# 3_v1.net
KiCad netlist of a schematic drawn in Altium Designer
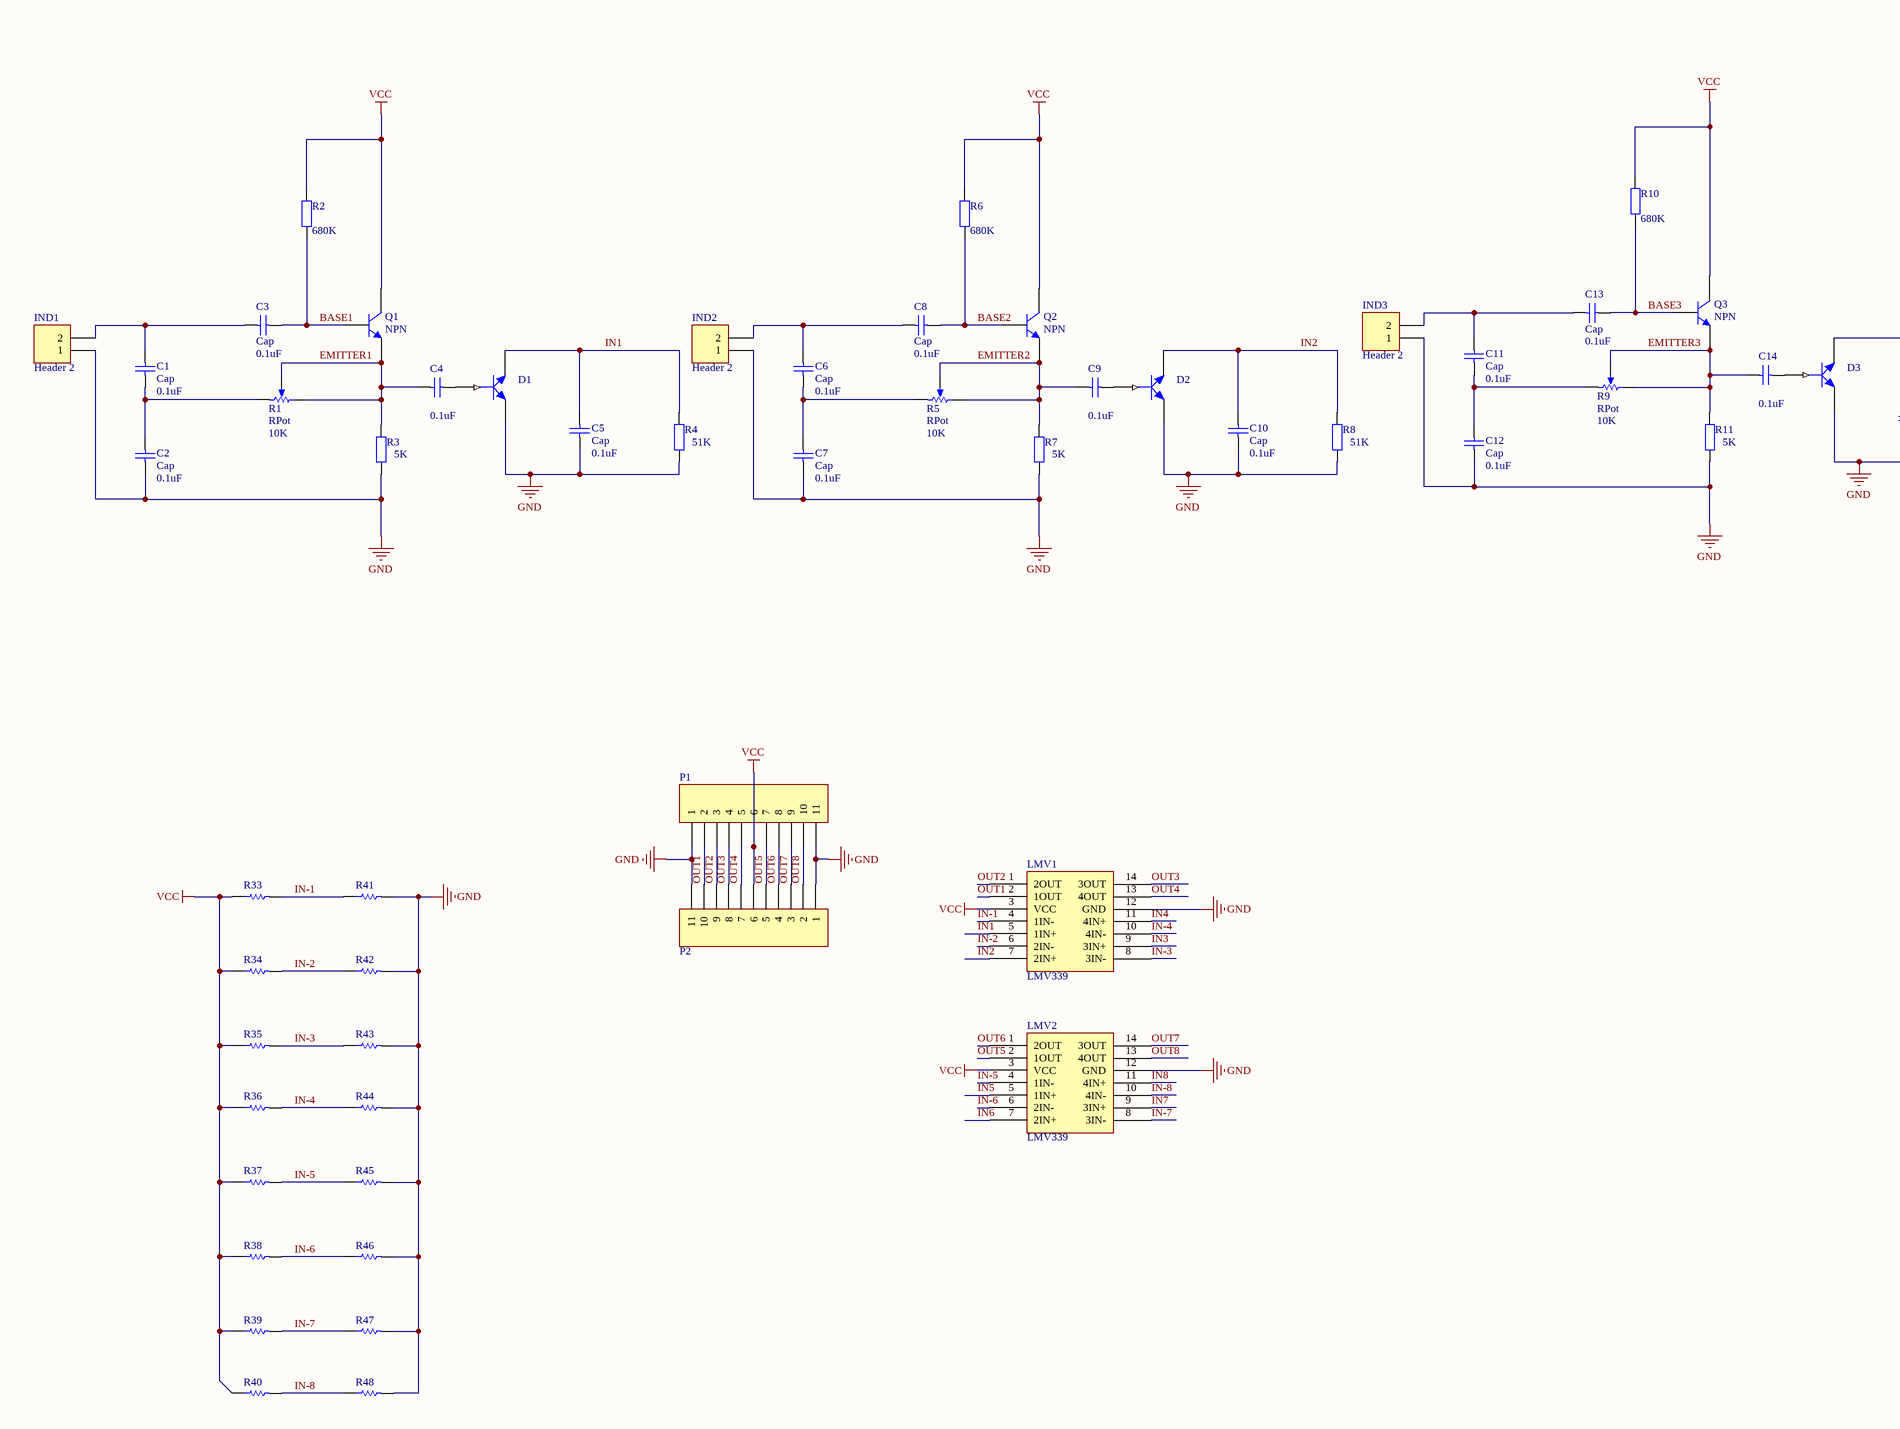
[diagram p0: 3点震荡v1.SchDoc, left]
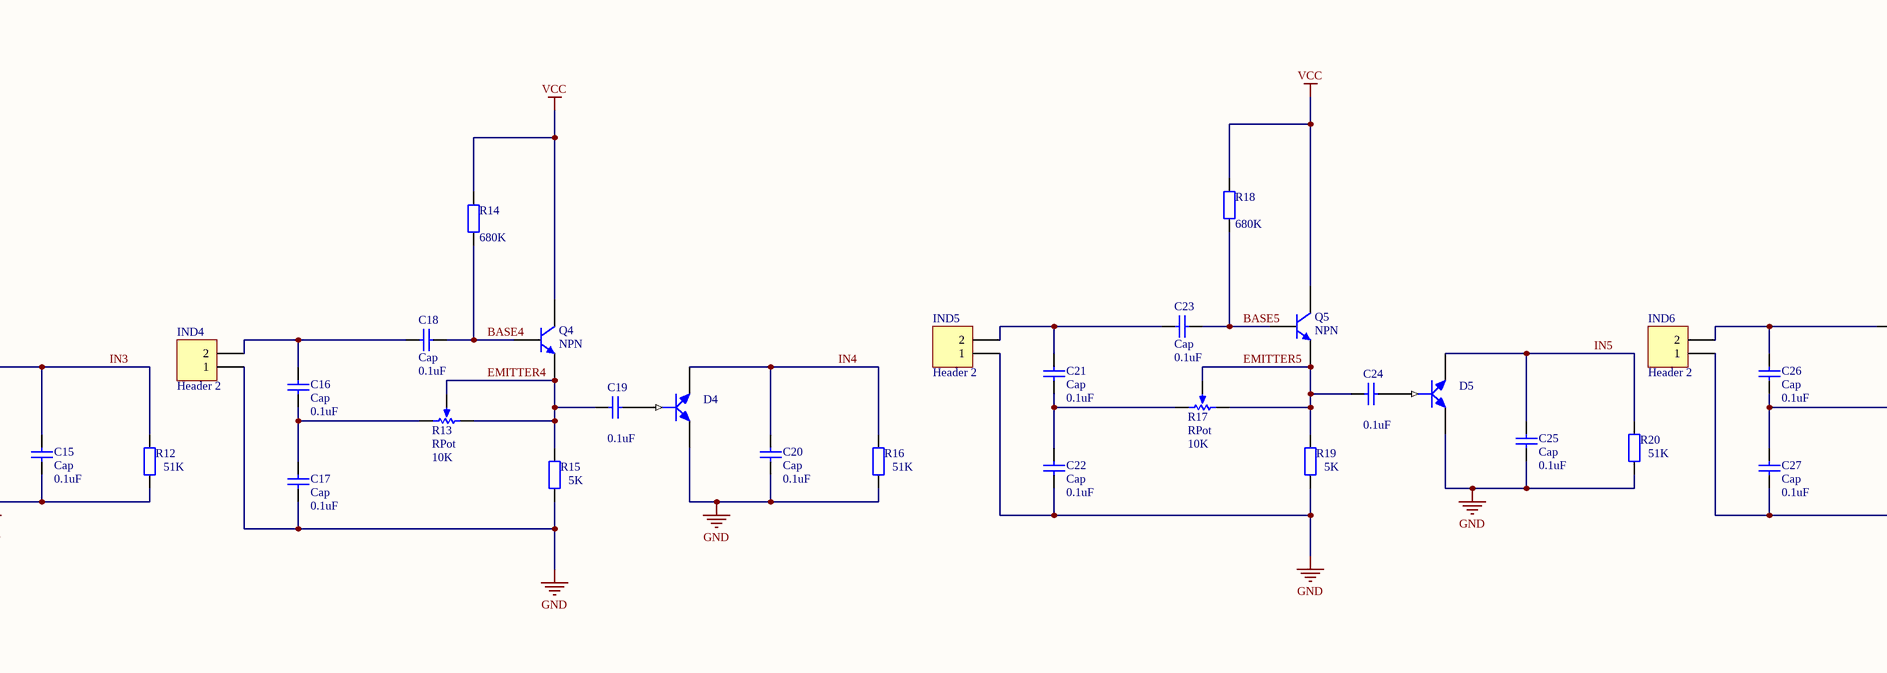
[diagram p1: 3点震荡v1.SchDoc, middle]
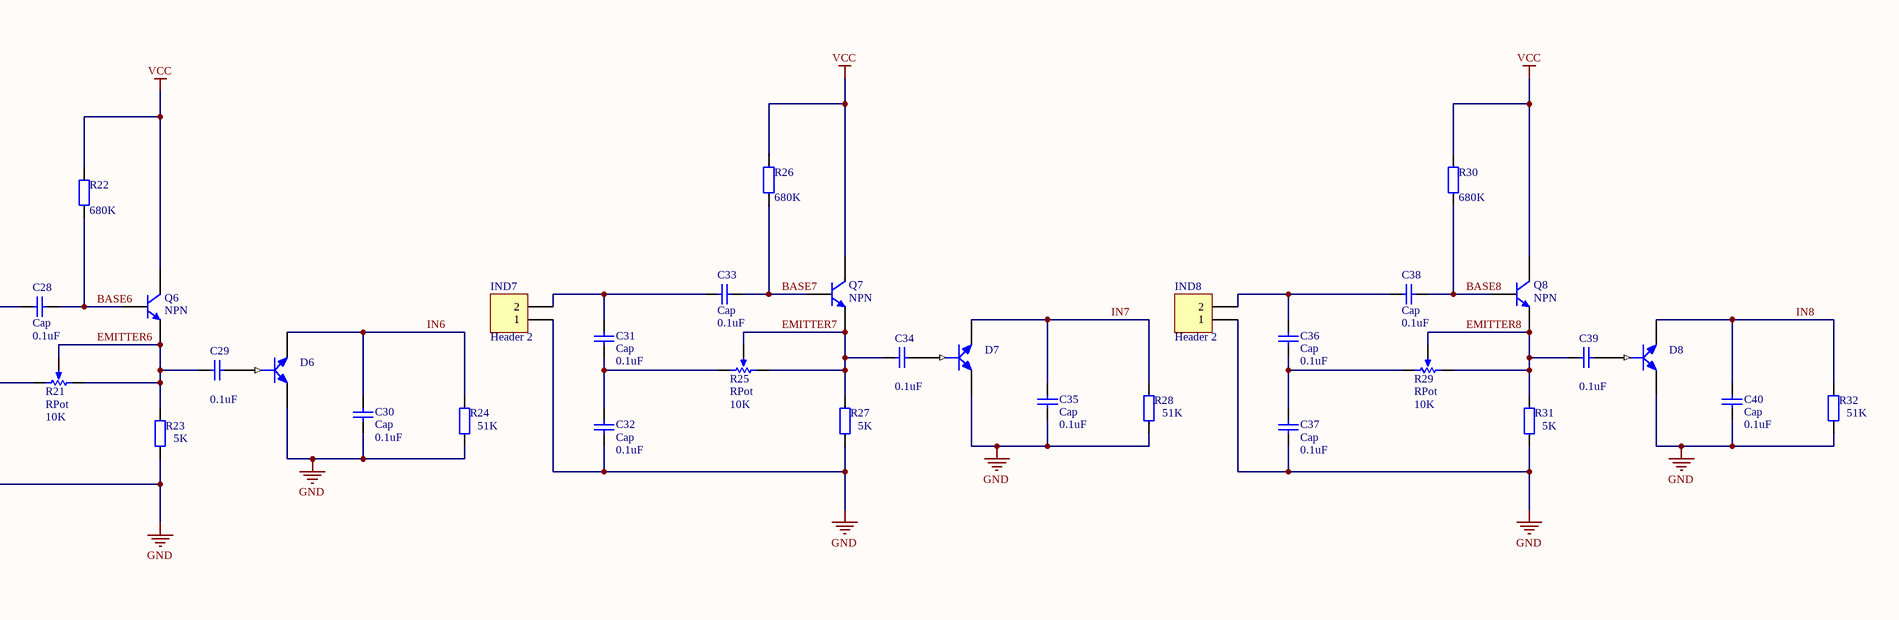
[diagram p2: 3点震荡v1.SchDoc, right]

(export (version "E")
  (design (tool "Eeschema 10.0.6"))
  (components
    (comp (ref "C1")
      (value "Cap")
      (footprint "C2012")
      (description "Capacitor")
      (fields (field (name "ALTIUM_VALUE") "0.1uF"))
      (libsource (lib "Miscellaneous Devices") (part "Cap"))
    )
    (comp (ref "C2")
      (value "Cap")
      (footprint "C2012")
      (description "Capacitor")
      (fields (field (name "ALTIUM_VALUE") "0.1uF"))
      (libsource (lib "Miscellaneous Devices") (part "Cap"))
    )
    (comp (ref "C3")
      (value "Cap")
      (footprint "C2012")
      (description "Capacitor")
      (fields (field (name "ALTIUM_VALUE") "0.1uF"))
      (libsource (lib "Miscellaneous Devices") (part "Cap"))
    )
    (comp (ref "C4")
      (value "0.1uF")
      (footprint "C2012")
      (description "Capacitor")
      (fields (field (name "Comment") "Cap"))
      (libsource (lib "Miscellaneous Devices") (part "Cap"))
    )
    (comp (ref "C5")
      (value "Cap")
      (footprint "c2012")
      (description "Capacitor")
      (fields (field (name "ALTIUM_VALUE") "0.1uF"))
      (libsource (lib "Miscellaneous Devices") (part "Cap"))
    )
    (comp (ref "C6")
      (value "Cap")
      (footprint "C2012")
      (description "Capacitor")
      (fields (field (name "ALTIUM_VALUE") "0.1uF"))
      (libsource (lib "Miscellaneous Devices") (part "Cap"))
    )
    (comp (ref "C7")
      (value "Cap")
      (footprint "C2012")
      (description "Capacitor")
      (fields (field (name "ALTIUM_VALUE") "0.1uF"))
      (libsource (lib "Miscellaneous Devices") (part "Cap"))
    )
    (comp (ref "C8")
      (value "Cap")
      (footprint "C2012")
      (description "Capacitor")
      (fields (field (name "ALTIUM_VALUE") "0.1uF"))
      (libsource (lib "Miscellaneous Devices") (part "Cap"))
    )
    (comp (ref "C9")
      (value "0.1uF")
      (footprint "C2012")
      (description "Capacitor")
      (fields (field (name "Comment") "Cap"))
      (libsource (lib "Miscellaneous Devices") (part "Cap"))
    )
    (comp (ref "C10")
      (value "Cap")
      (footprint "c2012")
      (description "Capacitor")
      (fields (field (name "ALTIUM_VALUE") "0.1uF"))
      (libsource (lib "Miscellaneous Devices") (part "Cap"))
    )
    (comp (ref "C11")
      (value "Cap")
      (footprint "C2012")
      (description "Capacitor")
      (fields (field (name "ALTIUM_VALUE") "0.1uF"))
      (libsource (lib "Miscellaneous Devices") (part "Cap"))
    )
    (comp (ref "C12")
      (value "Cap")
      (footprint "C2012")
      (description "Capacitor")
      (fields (field (name "ALTIUM_VALUE") "0.1uF"))
      (libsource (lib "Miscellaneous Devices") (part "Cap"))
    )
    (comp (ref "C13")
      (value "Cap")
      (footprint "C2012")
      (description "Capacitor")
      (fields (field (name "ALTIUM_VALUE") "0.1uF"))
      (libsource (lib "Miscellaneous Devices") (part "Cap"))
    )
    (comp (ref "C14")
      (value "0.1uF")
      (footprint "C2012")
      (description "Capacitor")
      (fields (field (name "Comment") "Cap"))
      (libsource (lib "Miscellaneous Devices") (part "Cap"))
    )
    (comp (ref "C15")
      (value "Cap")
      (footprint "c2012")
      (description "Capacitor")
      (fields (field (name "ALTIUM_VALUE") "0.1uF"))
      (libsource (lib "Miscellaneous Devices") (part "Cap"))
    )
    (comp (ref "C16")
      (value "Cap")
      (footprint "C2012")
      (description "Capacitor")
      (fields (field (name "ALTIUM_VALUE") "0.1uF"))
      (libsource (lib "Miscellaneous Devices") (part "Cap"))
    )
    (comp (ref "C17")
      (value "Cap")
      (footprint "C2012")
      (description "Capacitor")
      (fields (field (name "ALTIUM_VALUE") "0.1uF"))
      (libsource (lib "Miscellaneous Devices") (part "Cap"))
    )
    (comp (ref "C18")
      (value "Cap")
      (footprint "C2012")
      (description "Capacitor")
      (fields (field (name "ALTIUM_VALUE") "0.1uF"))
      (libsource (lib "Miscellaneous Devices") (part "Cap"))
    )
    (comp (ref "C19")
      (value "0.1uF")
      (footprint "C2012")
      (description "Capacitor")
      (fields (field (name "Comment") "Cap"))
      (libsource (lib "Miscellaneous Devices") (part "Cap"))
    )
    (comp (ref "C20")
      (value "Cap")
      (footprint "c2012")
      (description "Capacitor")
      (fields (field (name "ALTIUM_VALUE") "0.1uF"))
      (libsource (lib "Miscellaneous Devices") (part "Cap"))
    )
    (comp (ref "C21")
      (value "Cap")
      (footprint "C2012")
      (description "Capacitor")
      (fields (field (name "ALTIUM_VALUE") "0.1uF"))
      (libsource (lib "Miscellaneous Devices") (part "Cap"))
    )
    (comp (ref "C22")
      (value "Cap")
      (footprint "C2012")
      (description "Capacitor")
      (fields (field (name "ALTIUM_VALUE") "0.1uF"))
      (libsource (lib "Miscellaneous Devices") (part "Cap"))
    )
    (comp (ref "C23")
      (value "Cap")
      (footprint "C2012")
      (description "Capacitor")
      (fields (field (name "ALTIUM_VALUE") "0.1uF"))
      (libsource (lib "Miscellaneous Devices") (part "Cap"))
    )
    (comp (ref "C24")
      (value "0.1uF")
      (footprint "C2012")
      (description "Capacitor")
      (fields (field (name "Comment") "Cap"))
      (libsource (lib "Miscellaneous Devices") (part "Cap"))
    )
    (comp (ref "C25")
      (value "Cap")
      (footprint "c2012")
      (description "Capacitor")
      (fields (field (name "ALTIUM_VALUE") "0.1uF"))
      (libsource (lib "Miscellaneous Devices") (part "Cap"))
    )
    (comp (ref "C26")
      (value "Cap")
      (footprint "C2012")
      (description "Capacitor")
      (fields (field (name "ALTIUM_VALUE") "0.1uF"))
      (libsource (lib "Miscellaneous Devices") (part "Cap"))
    )
    (comp (ref "C27")
      (value "Cap")
      (footprint "C2012")
      (description "Capacitor")
      (fields (field (name "ALTIUM_VALUE") "0.1uF"))
      (libsource (lib "Miscellaneous Devices") (part "Cap"))
    )
    (comp (ref "C28")
      (value "Cap")
      (footprint "C2012")
      (description "Capacitor")
      (fields (field (name "ALTIUM_VALUE") "0.1uF"))
      (libsource (lib "Miscellaneous Devices") (part "Cap"))
    )
    (comp (ref "C29")
      (value "0.1uF")
      (footprint "C2012")
      (description "Capacitor")
      (fields (field (name "Comment") "Cap"))
      (libsource (lib "Miscellaneous Devices") (part "Cap"))
    )
    (comp (ref "C30")
      (value "Cap")
      (footprint "c2012")
      (description "Capacitor")
      (fields (field (name "ALTIUM_VALUE") "0.1uF"))
      (libsource (lib "Miscellaneous Devices") (part "Cap"))
    )
    (comp (ref "C31")
      (value "Cap")
      (footprint "C2012")
      (description "Capacitor")
      (fields (field (name "ALTIUM_VALUE") "0.1uF"))
      (libsource (lib "Miscellaneous Devices") (part "Cap"))
    )
    (comp (ref "C32")
      (value "Cap")
      (footprint "C2012")
      (description "Capacitor")
      (fields (field (name "ALTIUM_VALUE") "0.1uF"))
      (libsource (lib "Miscellaneous Devices") (part "Cap"))
    )
    (comp (ref "C33")
      (value "Cap")
      (footprint "C2012")
      (description "Capacitor")
      (fields (field (name "ALTIUM_VALUE") "0.1uF"))
      (libsource (lib "Miscellaneous Devices") (part "Cap"))
    )
    (comp (ref "C34")
      (value "0.1uF")
      (footprint "C2012")
      (description "Capacitor")
      (fields (field (name "Comment") "Cap"))
      (libsource (lib "Miscellaneous Devices") (part "Cap"))
    )
    (comp (ref "C35")
      (value "Cap")
      (footprint "c2012")
      (description "Capacitor")
      (fields (field (name "ALTIUM_VALUE") "0.1uF"))
      (libsource (lib "Miscellaneous Devices") (part "Cap"))
    )
    (comp (ref "C36")
      (value "Cap")
      (footprint "C2012")
      (description "Capacitor")
      (fields (field (name "ALTIUM_VALUE") "0.1uF"))
      (libsource (lib "Miscellaneous Devices") (part "Cap"))
    )
    (comp (ref "C37")
      (value "Cap")
      (footprint "C2012")
      (description "Capacitor")
      (fields (field (name "ALTIUM_VALUE") "0.1uF"))
      (libsource (lib "Miscellaneous Devices") (part "Cap"))
    )
    (comp (ref "C38")
      (value "Cap")
      (footprint "C2012")
      (description "Capacitor")
      (fields (field (name "ALTIUM_VALUE") "0.1uF"))
      (libsource (lib "Miscellaneous Devices") (part "Cap"))
    )
    (comp (ref "C39")
      (value "0.1uF")
      (footprint "C2012")
      (description "Capacitor")
      (fields (field (name "Comment") "Cap"))
      (libsource (lib "Miscellaneous Devices") (part "Cap"))
    )
    (comp (ref "C40")
      (value "Cap")
      (footprint "c2012")
      (description "Capacitor")
      (fields (field (name "ALTIUM_VALUE") "0.1uF"))
      (libsource (lib "Miscellaneous Devices") (part "Cap"))
    )
    (comp (ref "D1")
      (value "Diac-NPN")
      (footprint "SOT23_N")
      (description "DIAC")
      (libsource (lib "Miscellaneous Devices") (part "Diac-NPN"))
    )
    (comp (ref "D2")
      (value "Diac-NPN")
      (footprint "SOT23_N")
      (description "DIAC")
      (libsource (lib "Miscellaneous Devices") (part "Diac-NPN"))
    )
    (comp (ref "D3")
      (value "Diac-NPN")
      (footprint "SOT23_N")
      (description "DIAC")
      (libsource (lib "Miscellaneous Devices") (part "Diac-NPN"))
    )
    (comp (ref "D4")
      (value "Diac-NPN")
      (footprint "SOT23_N")
      (description "DIAC")
      (libsource (lib "Miscellaneous Devices") (part "Diac-NPN"))
    )
    (comp (ref "D5")
      (value "Diac-NPN")
      (footprint "SOT23_N")
      (description "DIAC")
      (libsource (lib "Miscellaneous Devices") (part "Diac-NPN"))
    )
    (comp (ref "D6")
      (value "Diac-NPN")
      (footprint "SOT23_N")
      (description "DIAC")
      (libsource (lib "Miscellaneous Devices") (part "Diac-NPN"))
    )
    (comp (ref "D7")
      (value "Diac-NPN")
      (footprint "SOT23_N")
      (description "DIAC")
      (libsource (lib "Miscellaneous Devices") (part "Diac-NPN"))
    )
    (comp (ref "D8")
      (value "Diac-NPN")
      (footprint "SOT23_N")
      (description "DIAC")
      (libsource (lib "Miscellaneous Devices") (part "Diac-NPN"))
    )
    (comp (ref "IND1")
      (value "Header 2")
      (footprint "HDR1X2")
      (description "Header, 2-Pin")
      (libsource (lib "Sparks") (part "Header 2"))
    )
    (comp (ref "IND2")
      (value "Header 2")
      (footprint "HDR1X2")
      (description "Header, 2-Pin")
      (libsource (lib "Sparks") (part "Header 2"))
    )
    (comp (ref "IND3")
      (value "Header 2")
      (footprint "HDR1X2")
      (description "Header, 2-Pin")
      (libsource (lib "Sparks") (part "Header 2"))
    )
    (comp (ref "IND4")
      (value "Header 2")
      (footprint "HDR1X2")
      (description "Header, 2-Pin")
      (libsource (lib "Sparks") (part "Header 2"))
    )
    (comp (ref "IND5")
      (value "Header 2")
      (footprint "HDR1X2")
      (description "Header, 2-Pin")
      (libsource (lib "Sparks") (part "Header 2"))
    )
    (comp (ref "IND6")
      (value "Header 2")
      (footprint "HDR1X2")
      (description "Header, 2-Pin")
      (libsource (lib "Sparks") (part "Header 2"))
    )
    (comp (ref "IND7")
      (value "Header 2")
      (footprint "HDR1X2")
      (description "Header, 2-Pin")
      (libsource (lib "Sparks") (part "Header 2"))
    )
    (comp (ref "IND8")
      (value "Header 2")
      (footprint "HDR1X2")
      (description "Header, 2-Pin")
      (libsource (lib "Sparks") (part "Header 2"))
    )
    (comp (ref "LMV1") (value "LMV339") (footprint "LMV339 TSSOP14") (libsource (lib "2号库") (part "LMV339")))
    (comp (ref "LMV2") (value "LMV339") (footprint "LMV339 TSSOP14") (libsource (lib "2号库") (part "LMV339")))
    (comp (ref "P1")
      (value "Header 11")
      (footprint "HDR1X11")
      (description "Header, 11-Pin")
      (libsource (lib "Sparks") (part "Header 11"))
    )
    (comp (ref "P2")
      (value "Header 11")
      (footprint "FFC/SM1.0-2H11")
      (description "Header, 11-Pin")
      (libsource (lib "") (part "Header 11_1"))
    )
    (comp (ref "Q1")
      (value "NPN")
      (footprint "SOT23_N")
      (description "NPN Bipolar Transistor")
      (libsource (lib "Miscellaneous Devices") (part "NPN"))
    )
    (comp (ref "Q2")
      (value "NPN")
      (footprint "SOT23_N")
      (description "NPN Bipolar Transistor")
      (libsource (lib "Miscellaneous Devices") (part "NPN"))
    )
    (comp (ref "Q3")
      (value "NPN")
      (footprint "SOT23_N")
      (description "NPN Bipolar Transistor")
      (libsource (lib "Miscellaneous Devices") (part "NPN"))
    )
    (comp (ref "Q4")
      (value "NPN")
      (footprint "SOT23_N")
      (description "NPN Bipolar Transistor")
      (libsource (lib "Miscellaneous Devices") (part "NPN"))
    )
    (comp (ref "Q5")
      (value "NPN")
      (footprint "SOT23_N")
      (description "NPN Bipolar Transistor")
      (libsource (lib "Miscellaneous Devices") (part "NPN"))
    )
    (comp (ref "Q6")
      (value "NPN")
      (footprint "SOT23_N")
      (description "NPN Bipolar Transistor")
      (libsource (lib "Miscellaneous Devices") (part "NPN"))
    )
    (comp (ref "Q7")
      (value "NPN")
      (footprint "SOT23_N")
      (description "NPN Bipolar Transistor")
      (libsource (lib "Miscellaneous Devices") (part "NPN"))
    )
    (comp (ref "Q8")
      (value "NPN")
      (footprint "SOT23_N")
      (description "NPN Bipolar Transistor")
      (libsource (lib "Miscellaneous Devices") (part "NPN"))
    )
    (comp (ref "R1")
      (value "RPot")
      (footprint "pot（长方形）")
      (description "Potentiometer")
      (fields (field (name "ALTIUM_VALUE") "10K"))
      (libsource (lib "Miscellaneous Devices") (part "RPot"))
    )
    (comp (ref "R2")
      (value "680K")
      (footprint "r2012")
      (description "Resistor")
      (fields (field (name "Comment") "Res2"))
      (libsource (lib "Miscellaneous Devices") (part "Res2"))
    )
    (comp (ref "R3")
      (value "5K")
      (footprint "R2012")
      (description "Resistor")
      (fields (field (name "Comment") "Res2"))
      (libsource (lib "Miscellaneous Devices") (part "Res2"))
    )
    (comp (ref "R4")
      (value "51K")
      (footprint "R2012")
      (description "Resistor")
      (fields (field (name "Comment") "Res2"))
      (libsource (lib "Miscellaneous Devices") (part "Res2"))
    )
    (comp (ref "R5")
      (value "RPot")
      (footprint "pot（长方形）")
      (description "Potentiometer")
      (fields (field (name "ALTIUM_VALUE") "10K"))
      (libsource (lib "Miscellaneous Devices") (part "RPot"))
    )
    (comp (ref "R6")
      (value "680K")
      (footprint "r2012")
      (description "Resistor")
      (fields (field (name "Comment") "Res2"))
      (libsource (lib "Miscellaneous Devices") (part "Res2"))
    )
    (comp (ref "R7")
      (value "5K")
      (footprint "R2012")
      (description "Resistor")
      (fields (field (name "Comment") "Res2"))
      (libsource (lib "Miscellaneous Devices") (part "Res2"))
    )
    (comp (ref "R8")
      (value "51K")
      (footprint "R2012")
      (description "Resistor")
      (fields (field (name "Comment") "Res2"))
      (libsource (lib "Miscellaneous Devices") (part "Res2"))
    )
    (comp (ref "R9")
      (value "RPot")
      (footprint "pot（长方形）")
      (description "Potentiometer")
      (fields (field (name "ALTIUM_VALUE") "10K"))
      (libsource (lib "Miscellaneous Devices") (part "RPot"))
    )
    (comp (ref "R10")
      (value "680K")
      (footprint "r2012")
      (description "Resistor")
      (fields (field (name "Comment") "Res2"))
      (libsource (lib "Miscellaneous Devices") (part "Res2"))
    )
    (comp (ref "R11")
      (value "5K")
      (footprint "R2012")
      (description "Resistor")
      (fields (field (name "Comment") "Res2"))
      (libsource (lib "Miscellaneous Devices") (part "Res2"))
    )
    (comp (ref "R12")
      (value "51K")
      (footprint "R2012")
      (description "Resistor")
      (fields (field (name "Comment") "Res2"))
      (libsource (lib "Miscellaneous Devices") (part "Res2"))
    )
    (comp (ref "R13")
      (value "RPot")
      (footprint "pot（长方形）")
      (description "Potentiometer")
      (fields (field (name "ALTIUM_VALUE") "10K"))
      (libsource (lib "Miscellaneous Devices") (part "RPot"))
    )
    (comp (ref "R14")
      (value "680K")
      (footprint "r2012")
      (description "Resistor")
      (fields (field (name "Comment") "Res2"))
      (libsource (lib "Miscellaneous Devices") (part "Res2"))
    )
    (comp (ref "R15")
      (value "5K")
      (footprint "R2012")
      (description "Resistor")
      (fields (field (name "Comment") "Res2"))
      (libsource (lib "Miscellaneous Devices") (part "Res2"))
    )
    (comp (ref "R16")
      (value "51K")
      (footprint "R2012")
      (description "Resistor")
      (fields (field (name "Comment") "Res2"))
      (libsource (lib "Miscellaneous Devices") (part "Res2"))
    )
    (comp (ref "R17")
      (value "RPot")
      (footprint "pot（长方形）")
      (description "Potentiometer")
      (fields (field (name "ALTIUM_VALUE") "10K"))
      (libsource (lib "Miscellaneous Devices") (part "RPot"))
    )
    (comp (ref "R18")
      (value "680K")
      (footprint "r2012")
      (description "Resistor")
      (fields (field (name "Comment") "Res2"))
      (libsource (lib "Miscellaneous Devices") (part "Res2"))
    )
    (comp (ref "R19")
      (value "5K")
      (footprint "R2012")
      (description "Resistor")
      (fields (field (name "Comment") "Res2"))
      (libsource (lib "Miscellaneous Devices") (part "Res2"))
    )
    (comp (ref "R20")
      (value "51K")
      (footprint "R2012")
      (description "Resistor")
      (fields (field (name "Comment") "Res2"))
      (libsource (lib "Miscellaneous Devices") (part "Res2"))
    )
    (comp (ref "R21")
      (value "RPot")
      (footprint "pot（长方形）")
      (description "Potentiometer")
      (fields (field (name "ALTIUM_VALUE") "10K"))
      (libsource (lib "Miscellaneous Devices") (part "RPot"))
    )
    (comp (ref "R22")
      (value "680K")
      (footprint "r2012")
      (description "Resistor")
      (fields (field (name "Comment") "Res2"))
      (libsource (lib "Miscellaneous Devices") (part "Res2"))
    )
    (comp (ref "R23")
      (value "5K")
      (footprint "R2012")
      (description "Resistor")
      (fields (field (name "Comment") "Res2"))
      (libsource (lib "Miscellaneous Devices") (part "Res2"))
    )
    (comp (ref "R24")
      (value "51K")
      (footprint "R2012")
      (description "Resistor")
      (fields (field (name "Comment") "Res2"))
      (libsource (lib "Miscellaneous Devices") (part "Res2"))
    )
    (comp (ref "R25")
      (value "RPot")
      (footprint "pot（长方形）")
      (description "Potentiometer")
      (fields (field (name "ALTIUM_VALUE") "10K"))
      (libsource (lib "Miscellaneous Devices") (part "RPot"))
    )
    (comp (ref "R26")
      (value "680K")
      (footprint "r2012")
      (description "Resistor")
      (fields (field (name "Comment") "Res2"))
      (libsource (lib "Miscellaneous Devices") (part "Res2"))
    )
    (comp (ref "R27")
      (value "5K")
      (footprint "R2012")
      (description "Resistor")
      (fields (field (name "Comment") "Res2"))
      (libsource (lib "Miscellaneous Devices") (part "Res2"))
    )
    (comp (ref "R28")
      (value "51K")
      (footprint "R2012")
      (description "Resistor")
      (fields (field (name "Comment") "Res2"))
      (libsource (lib "Miscellaneous Devices") (part "Res2"))
    )
    (comp (ref "R29")
      (value "RPot")
      (footprint "pot（长方形）")
      (description "Potentiometer")
      (fields (field (name "ALTIUM_VALUE") "10K"))
      (libsource (lib "Miscellaneous Devices") (part "RPot"))
    )
    (comp (ref "R30")
      (value "680K")
      (footprint "r2012")
      (description "Resistor")
      (fields (field (name "Comment") "Res2"))
      (libsource (lib "Miscellaneous Devices") (part "Res2"))
    )
    (comp (ref "R31")
      (value "5K")
      (footprint "R2012")
      (description "Resistor")
      (fields (field (name "Comment") "Res2"))
      (libsource (lib "Miscellaneous Devices") (part "Res2"))
    )
    (comp (ref "R32")
      (value "51K")
      (footprint "R2012")
      (description "Resistor")
      (fields (field (name "Comment") "Res2"))
      (libsource (lib "Miscellaneous Devices") (part "Res2"))
    )
    (comp (ref "R33")
      (value "Res")
      (footprint "R2012")
      (description "贴片电阻")
      (libsource (lib "Sparks") (part "Res"))
    )
    (comp (ref "R34")
      (value "Res")
      (footprint "R2012")
      (description "贴片电阻")
      (libsource (lib "Sparks") (part "Res"))
    )
    (comp (ref "R35")
      (value "Res")
      (footprint "R2012")
      (description "贴片电阻")
      (libsource (lib "Sparks") (part "Res"))
    )
    (comp (ref "R36")
      (value "Res")
      (footprint "R2012")
      (description "贴片电阻")
      (libsource (lib "Sparks") (part "Res"))
    )
    (comp (ref "R37")
      (value "Res")
      (footprint "R2012")
      (description "贴片电阻")
      (libsource (lib "Sparks") (part "Res"))
    )
    (comp (ref "R38")
      (value "Res")
      (footprint "R2012")
      (description "贴片电阻")
      (libsource (lib "Sparks") (part "Res"))
    )
    (comp (ref "R39")
      (value "Res")
      (footprint "R2012")
      (description "贴片电阻")
      (libsource (lib "Sparks") (part "Res"))
    )
    (comp (ref "R40")
      (value "Res")
      (footprint "R2012")
      (description "贴片电阻")
      (libsource (lib "Sparks") (part "Res"))
    )
    (comp (ref "R41")
      (value "Res")
      (footprint "R2012")
      (description "贴片电阻")
      (libsource (lib "Sparks") (part "Res"))
    )
    (comp (ref "R42")
      (value "Res")
      (footprint "R2012")
      (description "贴片电阻")
      (libsource (lib "Sparks") (part "Res"))
    )
    (comp (ref "R43")
      (value "Res")
      (footprint "R2012")
      (description "贴片电阻")
      (libsource (lib "Sparks") (part "Res"))
    )
    (comp (ref "R44")
      (value "Res")
      (footprint "R2012")
      (description "贴片电阻")
      (libsource (lib "Sparks") (part "Res"))
    )
    (comp (ref "R45")
      (value "Res")
      (footprint "R2012")
      (description "贴片电阻")
      (libsource (lib "Sparks") (part "Res"))
    )
    (comp (ref "R46")
      (value "Res")
      (footprint "R2012")
      (description "贴片电阻")
      (libsource (lib "Sparks") (part "Res"))
    )
    (comp (ref "R47")
      (value "Res")
      (footprint "R2012")
      (description "贴片电阻")
      (libsource (lib "Sparks") (part "Res"))
    )
    (comp (ref "R48")
      (value "Res")
      (footprint "R2012")
      (description "贴片电阻")
      (libsource (lib "Sparks") (part "Res"))
    )
  )
  (nets
    (net (code "1") (name "/BASE1") (class "Default")
      (node (ref "C3") (pin "1") (pinfunction "1_1") (pintype "passive"))
      (node (ref "Q1") (pin "2") (pinfunction "B_2") (pintype "passive"))
      (node (ref "R2") (pin "1") (pinfunction "1_1") (pintype "passive"))
    )
    (net (code "2") (name "/BASE2") (class "Default")
      (node (ref "C8") (pin "1") (pinfunction "1_1") (pintype "passive"))
      (node (ref "Q2") (pin "2") (pinfunction "B_2") (pintype "passive"))
      (node (ref "R6") (pin "1") (pinfunction "1_1") (pintype "passive"))
    )
    (net (code "3") (name "/BASE3") (class "Default")
      (node (ref "C13") (pin "1") (pinfunction "1_1") (pintype "passive"))
      (node (ref "Q3") (pin "2") (pinfunction "B_2") (pintype "passive"))
      (node (ref "R10") (pin "1") (pinfunction "1_1") (pintype "passive"))
    )
    (net (code "4") (name "/BASE4") (class "Default")
      (node (ref "C18") (pin "1") (pinfunction "1_1") (pintype "passive"))
      (node (ref "Q4") (pin "2") (pinfunction "B_2") (pintype "passive"))
      (node (ref "R14") (pin "1") (pinfunction "1_1") (pintype "passive"))
    )
    (net (code "5") (name "/BASE5") (class "Default")
      (node (ref "C23") (pin "1") (pinfunction "1_1") (pintype "passive"))
      (node (ref "Q5") (pin "2") (pinfunction "B_2") (pintype "passive"))
      (node (ref "R18") (pin "1") (pinfunction "1_1") (pintype "passive"))
    )
    (net (code "6") (name "/BASE6") (class "Default")
      (node (ref "C28") (pin "1") (pinfunction "1_1") (pintype "passive"))
      (node (ref "Q6") (pin "2") (pinfunction "B_2") (pintype "passive"))
      (node (ref "R22") (pin "1") (pinfunction "1_1") (pintype "passive"))
    )
    (net (code "7") (name "/BASE7") (class "Default")
      (node (ref "C33") (pin "1") (pinfunction "1_1") (pintype "passive"))
      (node (ref "Q7") (pin "2") (pinfunction "B_2") (pintype "passive"))
      (node (ref "R26") (pin "1") (pinfunction "1_1") (pintype "passive"))
    )
    (net (code "8") (name "/BASE8") (class "Default")
      (node (ref "C38") (pin "1") (pinfunction "1_1") (pintype "passive"))
      (node (ref "Q8") (pin "2") (pinfunction "B_2") (pintype "passive"))
      (node (ref "R30") (pin "1") (pinfunction "1_1") (pintype "passive"))
    )
    (net (code "9") (name "/EMITTER1") (class "Default")
      (node (ref "C4") (pin "1") (pinfunction "1_1") (pintype "passive"))
      (node (ref "Q1") (pin "3") (pinfunction "E_3") (pintype "passive"))
      (node (ref "R1") (pin "1") (pinfunction "TOP_1") (pintype "passive"))
      (node (ref "R1") (pin "3") (pinfunction "TAP_3") (pintype "passive"))
      (node (ref "R3") (pin "2") (pinfunction "2_2") (pintype "passive"))
    )
    (net (code "10") (name "/EMITTER2") (class "Default")
      (node (ref "C9") (pin "1") (pinfunction "1_1") (pintype "passive"))
      (node (ref "Q2") (pin "3") (pinfunction "E_3") (pintype "passive"))
      (node (ref "R5") (pin "1") (pinfunction "TOP_1") (pintype "passive"))
      (node (ref "R5") (pin "3") (pinfunction "TAP_3") (pintype "passive"))
      (node (ref "R7") (pin "2") (pinfunction "2_2") (pintype "passive"))
    )
    (net (code "11") (name "/EMITTER3") (class "Default")
      (node (ref "C14") (pin "1") (pinfunction "1_1") (pintype "passive"))
      (node (ref "Q3") (pin "3") (pinfunction "E_3") (pintype "passive"))
      (node (ref "R11") (pin "2") (pinfunction "2_2") (pintype "passive"))
      (node (ref "R9") (pin "1") (pinfunction "TOP_1") (pintype "passive"))
      (node (ref "R9") (pin "3") (pinfunction "TAP_3") (pintype "passive"))
    )
    (net (code "12") (name "/EMITTER4") (class "Default")
      (node (ref "C19") (pin "1") (pinfunction "1_1") (pintype "passive"))
      (node (ref "Q4") (pin "3") (pinfunction "E_3") (pintype "passive"))
      (node (ref "R13") (pin "1") (pinfunction "TOP_1") (pintype "passive"))
      (node (ref "R13") (pin "3") (pinfunction "TAP_3") (pintype "passive"))
      (node (ref "R15") (pin "2") (pinfunction "2_2") (pintype "passive"))
    )
    (net (code "13") (name "/EMITTER5") (class "Default")
      (node (ref "C24") (pin "1") (pinfunction "1_1") (pintype "passive"))
      (node (ref "Q5") (pin "3") (pinfunction "E_3") (pintype "passive"))
      (node (ref "R17") (pin "1") (pinfunction "TOP_1") (pintype "passive"))
      (node (ref "R17") (pin "3") (pinfunction "TAP_3") (pintype "passive"))
      (node (ref "R19") (pin "2") (pinfunction "2_2") (pintype "passive"))
    )
    (net (code "14") (name "/EMITTER6") (class "Default")
      (node (ref "C29") (pin "1") (pinfunction "1_1") (pintype "passive"))
      (node (ref "Q6") (pin "3") (pinfunction "E_3") (pintype "passive"))
      (node (ref "R21") (pin "1") (pinfunction "TOP_1") (pintype "passive"))
      (node (ref "R21") (pin "3") (pinfunction "TAP_3") (pintype "passive"))
      (node (ref "R23") (pin "2") (pinfunction "2_2") (pintype "passive"))
    )
    (net (code "15") (name "/EMITTER7") (class "Default")
      (node (ref "C34") (pin "1") (pinfunction "1_1") (pintype "passive"))
      (node (ref "Q7") (pin "3") (pinfunction "E_3") (pintype "passive"))
      (node (ref "R25") (pin "1") (pinfunction "TOP_1") (pintype "passive"))
      (node (ref "R25") (pin "3") (pinfunction "TAP_3") (pintype "passive"))
      (node (ref "R27") (pin "2") (pinfunction "2_2") (pintype "passive"))
    )
    (net (code "16") (name "/EMITTER8") (class "Default")
      (node (ref "C39") (pin "1") (pinfunction "1_1") (pintype "passive"))
      (node (ref "Q8") (pin "3") (pinfunction "E_3") (pintype "passive"))
      (node (ref "R29") (pin "1") (pinfunction "TOP_1") (pintype "passive"))
      (node (ref "R29") (pin "3") (pinfunction "TAP_3") (pintype "passive"))
      (node (ref "R31") (pin "2") (pinfunction "2_2") (pintype "passive"))
    )
    (net (code "17") (name "/IN-1") (class "Default")
      (node (ref "LMV1") (pin "4") (pinfunction "1IN-_4") (pintype "passive"))
      (node (ref "R33") (pin "2") (pinfunction "2_2") (pintype "passive"))
      (node (ref "R41") (pin "1") (pinfunction "1_1") (pintype "passive"))
    )
    (net (code "18") (name "/IN-2") (class "Default")
      (node (ref "LMV1") (pin "6") (pinfunction "2IN-_6") (pintype "passive"))
      (node (ref "R34") (pin "2") (pinfunction "2_2") (pintype "passive"))
      (node (ref "R42") (pin "1") (pinfunction "1_1") (pintype "passive"))
    )
    (net (code "19") (name "/IN-3") (class "Default")
      (node (ref "LMV1") (pin "8") (pinfunction "3IN-_8") (pintype "passive"))
      (node (ref "R35") (pin "2") (pinfunction "2_2") (pintype "passive"))
      (node (ref "R43") (pin "1") (pinfunction "1_1") (pintype "passive"))
    )
    (net (code "20") (name "/IN-4") (class "Default")
      (node (ref "LMV1") (pin "10") (pinfunction "4IN-_10") (pintype "passive"))
      (node (ref "R36") (pin "2") (pinfunction "2_2") (pintype "passive"))
      (node (ref "R44") (pin "1") (pinfunction "1_1") (pintype "passive"))
    )
    (net (code "21") (name "/IN-5") (class "Default")
      (node (ref "LMV2") (pin "4") (pinfunction "1IN-_4") (pintype "passive"))
      (node (ref "R37") (pin "2") (pinfunction "2_2") (pintype "passive"))
      (node (ref "R45") (pin "1") (pinfunction "1_1") (pintype "passive"))
    )
    (net (code "22") (name "/IN-6") (class "Default")
      (node (ref "LMV2") (pin "6") (pinfunction "2IN-_6") (pintype "passive"))
      (node (ref "R38") (pin "2") (pinfunction "2_2") (pintype "passive"))
      (node (ref "R46") (pin "1") (pinfunction "1_1") (pintype "passive"))
    )
    (net (code "23") (name "/IN-7") (class "Default")
      (node (ref "LMV2") (pin "8") (pinfunction "3IN-_8") (pintype "passive"))
      (node (ref "R39") (pin "2") (pinfunction "2_2") (pintype "passive"))
      (node (ref "R47") (pin "1") (pinfunction "1_1") (pintype "passive"))
    )
    (net (code "24") (name "/IN-8") (class "Default")
      (node (ref "LMV2") (pin "10") (pinfunction "4IN-_10") (pintype "passive"))
      (node (ref "R40") (pin "2") (pinfunction "2_2") (pintype "passive"))
      (node (ref "R48") (pin "1") (pinfunction "1_1") (pintype "passive"))
    )
    (net (code "25") (name "/IN1") (class "Default")
      (node (ref "C5") (pin "1") (pinfunction "1_1") (pintype "passive"))
      (node (ref "D1") (pin "2") (pinfunction "C_2") (pintype "passive"))
      (node (ref "LMV1") (pin "5") (pinfunction "1IN+_5") (pintype "passive"))
      (node (ref "R4") (pin "2") (pinfunction "2_2") (pintype "passive"))
    )
    (net (code "26") (name "/IN2") (class "Default")
      (node (ref "C10") (pin "1") (pinfunction "1_1") (pintype "passive"))
      (node (ref "D2") (pin "2") (pinfunction "C_2") (pintype "passive"))
      (node (ref "LMV1") (pin "7") (pinfunction "2IN+_7") (pintype "passive"))
      (node (ref "R8") (pin "2") (pinfunction "2_2") (pintype "passive"))
    )
    (net (code "27") (name "/IN3") (class "Default")
      (node (ref "C15") (pin "1") (pinfunction "1_1") (pintype "passive"))
      (node (ref "D3") (pin "2") (pinfunction "C_2") (pintype "passive"))
      (node (ref "LMV1") (pin "9") (pinfunction "3IN+_9") (pintype "passive"))
      (node (ref "R12") (pin "2") (pinfunction "2_2") (pintype "passive"))
    )
    (net (code "28") (name "/IN4") (class "Default")
      (node (ref "C20") (pin "1") (pinfunction "1_1") (pintype "passive"))
      (node (ref "D4") (pin "2") (pinfunction "C_2") (pintype "passive"))
      (node (ref "LMV1") (pin "11") (pinfunction "4IN+_11") (pintype "passive"))
      (node (ref "R16") (pin "2") (pinfunction "2_2") (pintype "passive"))
    )
    (net (code "29") (name "/IN5") (class "Default")
      (node (ref "C25") (pin "1") (pinfunction "1_1") (pintype "passive"))
      (node (ref "D5") (pin "2") (pinfunction "C_2") (pintype "passive"))
      (node (ref "LMV2") (pin "5") (pinfunction "1IN+_5") (pintype "passive"))
      (node (ref "R20") (pin "2") (pinfunction "2_2") (pintype "passive"))
    )
    (net (code "30") (name "/IN6") (class "Default")
      (node (ref "C30") (pin "1") (pinfunction "1_1") (pintype "passive"))
      (node (ref "D6") (pin "2") (pinfunction "C_2") (pintype "passive"))
      (node (ref "LMV2") (pin "7") (pinfunction "2IN+_7") (pintype "passive"))
      (node (ref "R24") (pin "2") (pinfunction "2_2") (pintype "passive"))
    )
    (net (code "31") (name "/IN7") (class "Default")
      (node (ref "C35") (pin "1") (pinfunction "1_1") (pintype "passive"))
      (node (ref "D7") (pin "2") (pinfunction "C_2") (pintype "passive"))
      (node (ref "LMV2") (pin "9") (pinfunction "3IN+_9") (pintype "passive"))
      (node (ref "R28") (pin "2") (pinfunction "2_2") (pintype "passive"))
    )
    (net (code "32") (name "/IN8") (class "Default")
      (node (ref "C40") (pin "1") (pinfunction "1_1") (pintype "passive"))
      (node (ref "D8") (pin "2") (pinfunction "C_2") (pintype "passive"))
      (node (ref "LMV2") (pin "11") (pinfunction "4IN+_11") (pintype "passive"))
      (node (ref "R32") (pin "2") (pinfunction "2_2") (pintype "passive"))
    )
    (net (code "33") (name "/OUT1") (class "Default")
      (node (ref "LMV1") (pin "2") (pinfunction "1OUT_2") (pintype "passive"))
      (node (ref "P1") (pin "2") (pinfunction "2_2") (pintype "passive"))
      (node (ref "P2") (pin "10") (pinfunction "10_10") (pintype "passive"))
    )
    (net (code "34") (name "/OUT2") (class "Default")
      (node (ref "LMV1") (pin "1") (pinfunction "2OUT_1") (pintype "passive"))
      (node (ref "P1") (pin "3") (pinfunction "3_3") (pintype "passive"))
      (node (ref "P2") (pin "9") (pinfunction "9_9") (pintype "passive"))
    )
    (net (code "35") (name "/OUT3") (class "Default")
      (node (ref "LMV1") (pin "14") (pinfunction "3OUT_14") (pintype "passive"))
      (node (ref "P1") (pin "4") (pinfunction "4_4") (pintype "passive"))
      (node (ref "P2") (pin "8") (pinfunction "8_8") (pintype "passive"))
    )
    (net (code "36") (name "/OUT4") (class "Default")
      (node (ref "LMV1") (pin "13") (pinfunction "4OUT_13") (pintype "passive"))
      (node (ref "P1") (pin "5") (pinfunction "5_5") (pintype "passive"))
      (node (ref "P2") (pin "7") (pinfunction "7_7") (pintype "passive"))
    )
    (net (code "37") (name "/OUT5") (class "Default")
      (node (ref "LMV2") (pin "2") (pinfunction "1OUT_2") (pintype "passive"))
      (node (ref "P1") (pin "7") (pinfunction "7_7") (pintype "passive"))
      (node (ref "P2") (pin "5") (pinfunction "5_5") (pintype "passive"))
    )
    (net (code "38") (name "/OUT6") (class "Default")
      (node (ref "LMV2") (pin "1") (pinfunction "2OUT_1") (pintype "passive"))
      (node (ref "P1") (pin "8") (pinfunction "8_8") (pintype "passive"))
      (node (ref "P2") (pin "4") (pinfunction "4_4") (pintype "passive"))
    )
    (net (code "39") (name "/OUT7") (class "Default")
      (node (ref "LMV2") (pin "14") (pinfunction "3OUT_14") (pintype "passive"))
      (node (ref "P1") (pin "9") (pinfunction "9_9") (pintype "passive"))
      (node (ref "P2") (pin "3") (pinfunction "3_3") (pintype "passive"))
    )
    (net (code "40") (name "/OUT8") (class "Default")
      (node (ref "LMV2") (pin "13") (pinfunction "4OUT_13") (pintype "passive"))
      (node (ref "P1") (pin "10") (pinfunction "10_10") (pintype "passive"))
      (node (ref "P2") (pin "2") (pinfunction "2_2") (pintype "passive"))
    )
    (net (code "41") (name "GND") (class "Default")
      (node (ref "C10") (pin "2") (pinfunction "2_2") (pintype "passive"))
      (node (ref "C12") (pin "2") (pinfunction "2_2") (pintype "passive"))
      (node (ref "C15") (pin "2") (pinfunction "2_2") (pintype "passive"))
      (node (ref "C17") (pin "2") (pinfunction "2_2") (pintype "passive"))
      (node (ref "C2") (pin "2") (pinfunction "2_2") (pintype "passive"))
      (node (ref "C20") (pin "2") (pinfunction "2_2") (pintype "passive"))
      (node (ref "C22") (pin "2") (pinfunction "2_2") (pintype "passive"))
      (node (ref "C25") (pin "2") (pinfunction "2_2") (pintype "passive"))
      (node (ref "C27") (pin "2") (pinfunction "2_2") (pintype "passive"))
      (node (ref "C30") (pin "2") (pinfunction "2_2") (pintype "passive"))
      (node (ref "C32") (pin "2") (pinfunction "2_2") (pintype "passive"))
      (node (ref "C35") (pin "2") (pinfunction "2_2") (pintype "passive"))
      (node (ref "C37") (pin "2") (pinfunction "2_2") (pintype "passive"))
      (node (ref "C40") (pin "2") (pinfunction "2_2") (pintype "passive"))
      (node (ref "C5") (pin "2") (pinfunction "2_2") (pintype "passive"))
      (node (ref "C7") (pin "2") (pinfunction "2_2") (pintype "passive"))
      (node (ref "D1") (pin "3") (pinfunction "E_3") (pintype "passive"))
      (node (ref "D2") (pin "3") (pinfunction "E_3") (pintype "passive"))
      (node (ref "D3") (pin "3") (pinfunction "E_3") (pintype "passive"))
      (node (ref "D4") (pin "3") (pinfunction "E_3") (pintype "passive"))
      (node (ref "D5") (pin "3") (pinfunction "E_3") (pintype "passive"))
      (node (ref "D6") (pin "3") (pinfunction "E_3") (pintype "passive"))
      (node (ref "D7") (pin "3") (pinfunction "E_3") (pintype "passive"))
      (node (ref "D8") (pin "3") (pinfunction "E_3") (pintype "passive"))
      (node (ref "IND1") (pin "1") (pinfunction "1_1") (pintype "passive"))
      (node (ref "IND2") (pin "1") (pinfunction "1_1") (pintype "passive"))
      (node (ref "IND3") (pin "1") (pinfunction "1_1") (pintype "passive"))
      (node (ref "IND4") (pin "1") (pinfunction "1_1") (pintype "passive"))
      (node (ref "IND5") (pin "1") (pinfunction "1_1") (pintype "passive"))
      (node (ref "IND6") (pin "1") (pinfunction "1_1") (pintype "passive"))
      (node (ref "IND7") (pin "1") (pinfunction "1_1") (pintype "passive"))
      (node (ref "IND8") (pin "1") (pinfunction "1_1") (pintype "passive"))
      (node (ref "LMV1") (pin "12") (pinfunction "GND_12") (pintype "passive"))
      (node (ref "LMV2") (pin "12") (pinfunction "GND_12") (pintype "passive"))
      (node (ref "P1") (pin "1") (pinfunction "1_1") (pintype "passive"))
      (node (ref "P1") (pin "11") (pinfunction "11_11") (pintype "passive"))
      (node (ref "P2") (pin "1") (pinfunction "1_1") (pintype "passive"))
      (node (ref "P2") (pin "11") (pinfunction "11_11") (pintype "passive"))
      (node (ref "R11") (pin "1") (pinfunction "1_1") (pintype "passive"))
      (node (ref "R12") (pin "1") (pinfunction "1_1") (pintype "passive"))
      (node (ref "R15") (pin "1") (pinfunction "1_1") (pintype "passive"))
      (node (ref "R16") (pin "1") (pinfunction "1_1") (pintype "passive"))
      (node (ref "R19") (pin "1") (pinfunction "1_1") (pintype "passive"))
      (node (ref "R20") (pin "1") (pinfunction "1_1") (pintype "passive"))
      (node (ref "R23") (pin "1") (pinfunction "1_1") (pintype "passive"))
      (node (ref "R24") (pin "1") (pinfunction "1_1") (pintype "passive"))
      (node (ref "R27") (pin "1") (pinfunction "1_1") (pintype "passive"))
      (node (ref "R28") (pin "1") (pinfunction "1_1") (pintype "passive"))
      (node (ref "R3") (pin "1") (pinfunction "1_1") (pintype "passive"))
      (node (ref "R31") (pin "1") (pinfunction "1_1") (pintype "passive"))
      (node (ref "R32") (pin "1") (pinfunction "1_1") (pintype "passive"))
      (node (ref "R4") (pin "1") (pinfunction "1_1") (pintype "passive"))
      (node (ref "R41") (pin "2") (pinfunction "2_2") (pintype "passive"))
      (node (ref "R42") (pin "2") (pinfunction "2_2") (pintype "passive"))
      (node (ref "R43") (pin "2") (pinfunction "2_2") (pintype "passive"))
      (node (ref "R44") (pin "2") (pinfunction "2_2") (pintype "passive"))
      (node (ref "R45") (pin "2") (pinfunction "2_2") (pintype "passive"))
      (node (ref "R46") (pin "2") (pinfunction "2_2") (pintype "passive"))
      (node (ref "R47") (pin "2") (pinfunction "2_2") (pintype "passive"))
      (node (ref "R48") (pin "2") (pinfunction "2_2") (pintype "passive"))
      (node (ref "R7") (pin "1") (pinfunction "1_1") (pintype "passive"))
      (node (ref "R8") (pin "1") (pinfunction "1_1") (pintype "passive"))
    )
    (net (code "42") (name "Net-(C1-Pad1)") (class "Default")
      (node (ref "C1") (pin "1") (pinfunction "1_1") (pintype "passive"))
      (node (ref "C3") (pin "2") (pinfunction "2_2") (pintype "passive"))
      (node (ref "IND1") (pin "2") (pinfunction "2_2") (pintype "passive"))
    )
    (net (code "43") (name "Net-(C6-Pad1)") (class "Default")
      (node (ref "C6") (pin "1") (pinfunction "1_1") (pintype "passive"))
      (node (ref "C8") (pin "2") (pinfunction "2_2") (pintype "passive"))
      (node (ref "IND2") (pin "2") (pinfunction "2_2") (pintype "passive"))
    )
    (net (code "44") (name "Net-(C11-Pad1)") (class "Default")
      (node (ref "C11") (pin "1") (pinfunction "1_1") (pintype "passive"))
      (node (ref "C13") (pin "2") (pinfunction "2_2") (pintype "passive"))
      (node (ref "IND3") (pin "2") (pinfunction "2_2") (pintype "passive"))
    )
    (net (code "45") (name "Net-(C16-Pad1)") (class "Default")
      (node (ref "C16") (pin "1") (pinfunction "1_1") (pintype "passive"))
      (node (ref "C18") (pin "2") (pinfunction "2_2") (pintype "passive"))
      (node (ref "IND4") (pin "2") (pinfunction "2_2") (pintype "passive"))
    )
    (net (code "46") (name "Net-(C21-Pad1)") (class "Default")
      (node (ref "C21") (pin "1") (pinfunction "1_1") (pintype "passive"))
      (node (ref "C23") (pin "2") (pinfunction "2_2") (pintype "passive"))
      (node (ref "IND5") (pin "2") (pinfunction "2_2") (pintype "passive"))
    )
    (net (code "47") (name "Net-(C26-Pad1)") (class "Default")
      (node (ref "C26") (pin "1") (pinfunction "1_1") (pintype "passive"))
      (node (ref "C28") (pin "2") (pinfunction "2_2") (pintype "passive"))
      (node (ref "IND6") (pin "2") (pinfunction "2_2") (pintype "passive"))
    )
    (net (code "48") (name "Net-(C31-Pad1)") (class "Default")
      (node (ref "C31") (pin "1") (pinfunction "1_1") (pintype "passive"))
      (node (ref "C33") (pin "2") (pinfunction "2_2") (pintype "passive"))
      (node (ref "IND7") (pin "2") (pinfunction "2_2") (pintype "passive"))
    )
    (net (code "49") (name "Net-(C36-Pad1)") (class "Default")
      (node (ref "C36") (pin "1") (pinfunction "1_1") (pintype "passive"))
      (node (ref "C38") (pin "2") (pinfunction "2_2") (pintype "passive"))
      (node (ref "IND8") (pin "2") (pinfunction "2_2") (pintype "passive"))
    )
    (net (code "50") (name "Net-(D1-B)") (class "Default")
      (node (ref "C4") (pin "2") (pinfunction "2_2") (pintype "passive"))
      (node (ref "D1") (pin "1") (pinfunction "B_1") (pintype "input"))
    )
    (net (code "51") (name "Net-(D2-B)") (class "Default")
      (node (ref "C9") (pin "2") (pinfunction "2_2") (pintype "passive"))
      (node (ref "D2") (pin "1") (pinfunction "B_1") (pintype "input"))
    )
    (net (code "52") (name "Net-(D3-B)") (class "Default")
      (node (ref "C14") (pin "2") (pinfunction "2_2") (pintype "passive"))
      (node (ref "D3") (pin "1") (pinfunction "B_1") (pintype "input"))
    )
    (net (code "53") (name "Net-(D4-B)") (class "Default")
      (node (ref "C19") (pin "2") (pinfunction "2_2") (pintype "passive"))
      (node (ref "D4") (pin "1") (pinfunction "B_1") (pintype "input"))
    )
    (net (code "54") (name "Net-(D5-B)") (class "Default")
      (node (ref "C24") (pin "2") (pinfunction "2_2") (pintype "passive"))
      (node (ref "D5") (pin "1") (pinfunction "B_1") (pintype "input"))
    )
    (net (code "55") (name "Net-(D6-B)") (class "Default")
      (node (ref "C29") (pin "2") (pinfunction "2_2") (pintype "passive"))
      (node (ref "D6") (pin "1") (pinfunction "B_1") (pintype "input"))
    )
    (net (code "56") (name "Net-(D7-B)") (class "Default")
      (node (ref "C34") (pin "2") (pinfunction "2_2") (pintype "passive"))
      (node (ref "D7") (pin "1") (pinfunction "B_1") (pintype "input"))
    )
    (net (code "57") (name "Net-(D8-B)") (class "Default")
      (node (ref "C39") (pin "2") (pinfunction "2_2") (pintype "passive"))
      (node (ref "D8") (pin "1") (pinfunction "B_1") (pintype "input"))
    )
    (net (code "58") (name "Net-(R1-BOT)") (class "Default")
      (node (ref "C1") (pin "2") (pinfunction "2_2") (pintype "passive"))
      (node (ref "C2") (pin "1") (pinfunction "1_1") (pintype "passive"))
      (node (ref "R1") (pin "2") (pinfunction "BOT_2") (pintype "passive"))
    )
    (net (code "59") (name "Net-(R5-BOT)") (class "Default")
      (node (ref "C6") (pin "2") (pinfunction "2_2") (pintype "passive"))
      (node (ref "C7") (pin "1") (pinfunction "1_1") (pintype "passive"))
      (node (ref "R5") (pin "2") (pinfunction "BOT_2") (pintype "passive"))
    )
    (net (code "60") (name "Net-(R9-BOT)") (class "Default")
      (node (ref "C11") (pin "2") (pinfunction "2_2") (pintype "passive"))
      (node (ref "C12") (pin "1") (pinfunction "1_1") (pintype "passive"))
      (node (ref "R9") (pin "2") (pinfunction "BOT_2") (pintype "passive"))
    )
    (net (code "61") (name "Net-(R13-BOT)") (class "Default")
      (node (ref "C16") (pin "2") (pinfunction "2_2") (pintype "passive"))
      (node (ref "C17") (pin "1") (pinfunction "1_1") (pintype "passive"))
      (node (ref "R13") (pin "2") (pinfunction "BOT_2") (pintype "passive"))
    )
    (net (code "62") (name "Net-(R17-BOT)") (class "Default")
      (node (ref "C21") (pin "2") (pinfunction "2_2") (pintype "passive"))
      (node (ref "C22") (pin "1") (pinfunction "1_1") (pintype "passive"))
      (node (ref "R17") (pin "2") (pinfunction "BOT_2") (pintype "passive"))
    )
    (net (code "63") (name "Net-(R21-BOT)") (class "Default")
      (node (ref "C26") (pin "2") (pinfunction "2_2") (pintype "passive"))
      (node (ref "C27") (pin "1") (pinfunction "1_1") (pintype "passive"))
      (node (ref "R21") (pin "2") (pinfunction "BOT_2") (pintype "passive"))
    )
    (net (code "64") (name "Net-(R25-BOT)") (class "Default")
      (node (ref "C31") (pin "2") (pinfunction "2_2") (pintype "passive"))
      (node (ref "C32") (pin "1") (pinfunction "1_1") (pintype "passive"))
      (node (ref "R25") (pin "2") (pinfunction "BOT_2") (pintype "passive"))
    )
    (net (code "65") (name "Net-(R29-BOT)") (class "Default")
      (node (ref "C36") (pin "2") (pinfunction "2_2") (pintype "passive"))
      (node (ref "C37") (pin "1") (pinfunction "1_1") (pintype "passive"))
      (node (ref "R29") (pin "2") (pinfunction "BOT_2") (pintype "passive"))
    )
    (net (code "66") (name "VCC") (class "Default")
      (node (ref "LMV1") (pin "3") (pinfunction "VCC_3") (pintype "passive"))
      (node (ref "LMV2") (pin "3") (pinfunction "VCC_3") (pintype "passive"))
      (node (ref "P1") (pin "6") (pinfunction "6_6") (pintype "passive"))
      (node (ref "P2") (pin "6") (pinfunction "6_6") (pintype "passive"))
      (node (ref "Q1") (pin "1") (pinfunction "C_1") (pintype "passive"))
      (node (ref "Q2") (pin "1") (pinfunction "C_1") (pintype "passive"))
      (node (ref "Q3") (pin "1") (pinfunction "C_1") (pintype "passive"))
      (node (ref "Q4") (pin "1") (pinfunction "C_1") (pintype "passive"))
      (node (ref "Q5") (pin "1") (pinfunction "C_1") (pintype "passive"))
      (node (ref "Q6") (pin "1") (pinfunction "C_1") (pintype "passive"))
      (node (ref "Q7") (pin "1") (pinfunction "C_1") (pintype "passive"))
      (node (ref "Q8") (pin "1") (pinfunction "C_1") (pintype "passive"))
      (node (ref "R10") (pin "2") (pinfunction "2_2") (pintype "passive"))
      (node (ref "R14") (pin "2") (pinfunction "2_2") (pintype "passive"))
      (node (ref "R18") (pin "2") (pinfunction "2_2") (pintype "passive"))
      (node (ref "R2") (pin "2") (pinfunction "2_2") (pintype "passive"))
      (node (ref "R22") (pin "2") (pinfunction "2_2") (pintype "passive"))
      (node (ref "R26") (pin "2") (pinfunction "2_2") (pintype "passive"))
      (node (ref "R30") (pin "2") (pinfunction "2_2") (pintype "passive"))
      (node (ref "R33") (pin "1") (pinfunction "1_1") (pintype "passive"))
      (node (ref "R34") (pin "1") (pinfunction "1_1") (pintype "passive"))
      (node (ref "R35") (pin "1") (pinfunction "1_1") (pintype "passive"))
      (node (ref "R36") (pin "1") (pinfunction "1_1") (pintype "passive"))
      (node (ref "R37") (pin "1") (pinfunction "1_1") (pintype "passive"))
      (node (ref "R38") (pin "1") (pinfunction "1_1") (pintype "passive"))
      (node (ref "R39") (pin "1") (pinfunction "1_1") (pintype "passive"))
      (node (ref "R40") (pin "1") (pinfunction "1_1") (pintype "passive"))
      (node (ref "R6") (pin "2") (pinfunction "2_2") (pintype "passive"))
    )
  )
)
